# 7_dc_dc_3v3_eps_ttc.net
KiCad netlist of a schematic drawn in Altium Designer
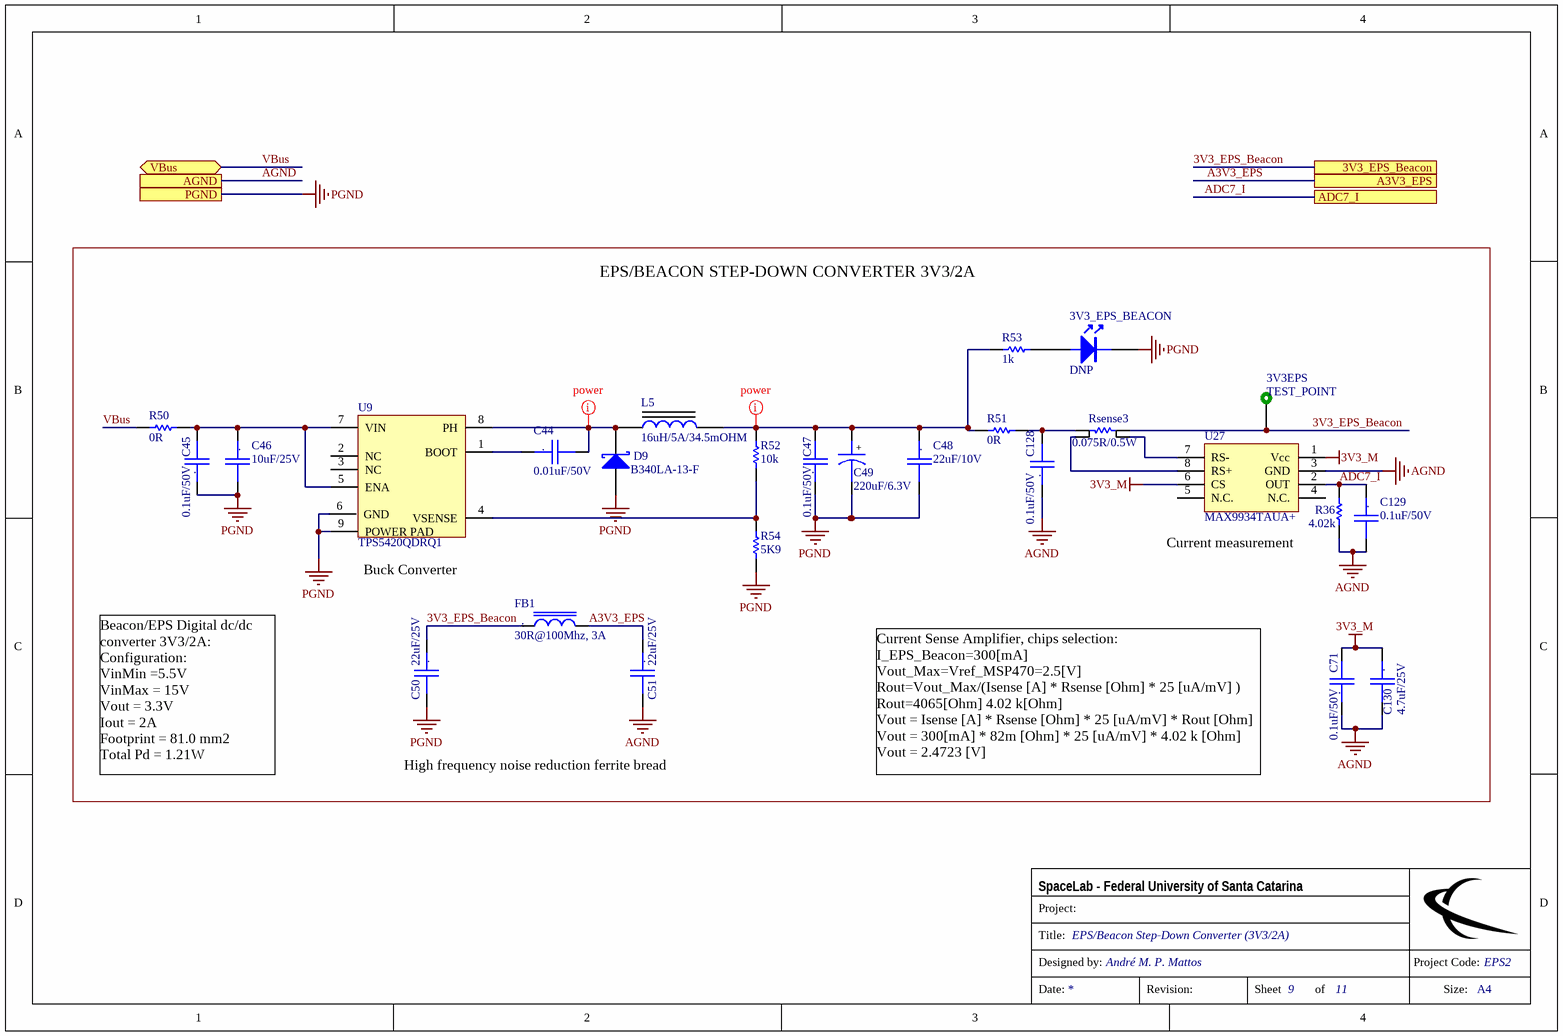
[diagram p0: 7_dc_dc_3v3_eps_ttc.schdoc]

(export (version "E")
  (design (tool "Eeschema 10.0.6"))
  (components
    (comp (ref "3V3EPS")
      (value "TEST_POINT")
      (footprint "TEST_POINT")
      (description "Test point")
      (libsource (lib "PCB_Project_FlightModel_EPS") (part "TEST_POINT"))
    )
    (comp (ref "3V3_EPS_BEACON")
      (value "DNP")
      (footprint "0603-LED")
      (description "SMD Green LED")
      (fields (field (name "PARTNUMBER") "150060VS75000") (field (name "MANUFACTURER") "Wurth Electronics"))
      (libsource (lib "PCB_Project_FlightModel_EPS") (part "LED/G_0603"))
    )
    (comp (ref "C44")
      (value "0.01uF/50V")
      (footprint "CC0805")
      (description "CAP CER 0.01uF 50V 10% X7R 0805")
      (fields (field (name "PARTNUMBER") "08055C103KAT4A") (field (name "MANUFACTURER") "Kyocera AVX"))
      (libsource (lib "PCB_Project_FlightModel_EPS") (part "Cap_Cer_X7R_0.01uF_50V_0805"))
    )
    (comp (ref "C45")
      (value "0.1uF/50V")
      (footprint "CC0805")
      (description "CAP CER 0.1UF 50V 10% X7R 0805")
      (fields (field (name "PARTNUMBER") "CC0805KRX7R9BB104") (field (name "MANUFACTURER") "Yageo"))
      (libsource (lib "PCB_Project_FlightModel_EPS") (part "Cap_Cer_X7R_0.1uF_50V_0805"))
    )
    (comp (ref "C46")
      (value "10uF/25V")
      (footprint "CC1206")
      (description "CAP CER 10uF 25V 10% X7R 1206")
      (fields (field (name "PARTNUMBER") "GRM31CR71E106KA12L") (field (name "MANUFACTURER") "Murata"))
      (libsource (lib "PCB_Project_FlightModel_EPS") (part "Cap_Cer_X7R_10uF_25V_1206"))
    )
    (comp (ref "C47")
      (value "0.1uF/50V")
      (footprint "CC0805")
      (description "CAP CER 0.1UF 50V 10% X7R 0805")
      (fields (field (name "PARTNUMBER") "CC0805KRX7R9BB104") (field (name "MANUFACTURER") "Yageo"))
      (libsource (lib "PCB_Project_FlightModel_EPS") (part "Cap_Cer_X7R_0.1uF_50V_0805"))
    )
    (comp (ref "C48")
      (value "22uF/10V")
      (footprint "CC1206")
      (description "CAP CER 22uF 10V 10% X7R 1206")
      (fields (field (name "PARTNUMBER") "GRM31CR71A226KE15L") (field (name "MANUFACTURER") "Murata"))
      (libsource (lib "PCB_Project_FlightModel_EPS") (part "Cap_Cer_X7R_22uF_10V_1206"))
    )
    (comp (ref "C49")
      (value "220uF/6.3V")
      (footprint "FloripaSatPcbLib:cc1210")
      (description "CAP Tantalum 220uF 6.3V 20% 1210")
      (fields (field (name "PARTNUMBER") "6TPE220MAZB") (field (name "MANUFACTURER") "Panasonic"))
      (libsource (lib "PCB_Project_FlightModel_EPS") (part "Cap_Tant_SMD_220uF_6.3V_1210"))
    )
    (comp (ref "C50")
      (value "22uF/25V")
      (footprint "CC1210")
      (description "CAP CER 22uF 25V 10% X7R 1210")
      (fields (field (name "PARTNUMBER") "GRM32ER71E226KE15L") (field (name "MANUFACTURER") "Murata"))
      (libsource (lib "PCB_Project_FlightModel_EPS") (part "Cap_Cer_X7R_22uF_25V_1210"))
    )
    (comp (ref "C51")
      (value "22uF/25V")
      (footprint "CC1210")
      (description "CAP CER 22uF 25V 10% X7R 1210")
      (fields (field (name "PARTNUMBER") "GRM32ER71E226KE15L") (field (name "MANUFACTURER") "Murata"))
      (libsource (lib "PCB_Project_FlightModel_EPS") (part "Cap_Cer_X7R_22uF_25V_1210"))
    )
    (comp (ref "C71")
      (value "0.1uF/50V")
      (footprint "CC0603")
      (description "CAP CER 0.1UF 50V 10% X7R 0603")
      (fields (field (name "PARTNUMBER") "CC0603KPX7R9BB104") (field (name "MANUFACTURER") "Yageo"))
      (libsource (lib "PCB_Project_FlightModel_EPS") (part "Cap_Cer_X7R_0.1uF_50V_0603"))
    )
    (comp (ref "C128")
      (value "0.1uF/50V")
      (footprint "CC0603")
      (description "CAP CER 0.1UF 50V 10% X7R 0603")
      (fields (field (name "PARTNUMBER") "CC0603KPX7R9BB104") (field (name "MANUFACTURER") "Yageo"))
      (libsource (lib "PCB_Project_FlightModel_EPS") (part "Cap_Cer_X7R_0.1uF_50V_0603"))
    )
    (comp (ref "C129")
      (value "0.1uF/50V")
      (footprint "CC0603")
      (description "CAP CER 0.1UF 50V 10% X7R 0603")
      (fields (field (name "PARTNUMBER") "CC0603KPX7R9BB104") (field (name "MANUFACTURER") "Yageo"))
      (libsource (lib "PCB_Project_FlightModel_EPS") (part "Cap_Cer_X7R_0.1uF_50V_0603"))
    )
    (comp (ref "C130")
      (value "4.7uF/25V")
      (footprint "CC0805")
      (description "CAP CER 4.7uF 25V 10% X7R 0805")
      (fields (field (name "PARTNUMBER") "CC0805KKX7R8BB475") (field (name "MANUFACTURER") "Yageo"))
      (libsource (lib "PCB_Project_FlightModel_EPS") (part "Cap_Cer_X7R_4.7uF_25V_0805"))
    )
    (comp (ref "D9")
      (value "B340LA-13-F")
      (footprint "DO-214AC")
      (description "DIODE SCHOTTKY 40V 3A B340LA-13-F")
      (fields (field (name "MANUFACTURER") "Diodes"))
      (libsource (lib "PCB_Project_FlightModel_EPS") (part "DIODE_SCHOTTKY_40V_3A_B340LA-13-F"))
    )
    (comp (ref "FB1")
      (value "30R@100Mhz, 3A")
      (footprint "IND0805")
      (description "Ferrite Bead 30 OHM 3A 100MHz")
      (fields (field (name "PARTNUMBER") "BLM21PG300SN1D") (field (name "MANUFACTURER") "Murata"))
      (libsource (lib "PCB_Project_FlightModel_EPS") (part "FB_30R_3A_100MHz_0805"))
    )
    (comp (ref "L5")
      (value "16uH/5A/34.5mOHM")
      (footprint "IND_744325xxx")
      (description "INDUCTOR 16UH 5A SMD")
      (fields (field (name "PARTNUMBER") "7443251600") (field (name "MANUFACTURER") "Wurth Electronics"))
      (libsource (lib "PCB_Project_FlightModel_EPS") (part "IND_POWER_16uH_5A_35.5mR"))
    )
    (comp (ref "R36")
      (value "4.02k")
      (footprint "0805")
      (description "RES 4.02k OHM 1/8W 0.1% 0805")
      (fields (field (name "PARTNUMBER") "ERA-6AEB4021V") (field (name "MANUFACTURER") "Panasonic"))
      (libsource (lib "PCB_Project_FlightModel_EPS") (part "R4.02k_0.1%_1/8W_0805"))
    )
    (comp (ref "R50")
      (value "0R")
      (footprint "1206")
      (description "RES 0.0 OHM 3/4W JUMP 1206")
      (fields
        (field (name "PARTNUMBER") "HCJ1206ZT0R00")
        (field (name "MANUFACTURER") "Stackpole Electronics")
      )
      (libsource (lib "PCB_Project_FlightModel_EPS") (part "R0R_JUMPER_3/4W_1206"))
    )
    (comp (ref "R51")
      (value "0R")
      (footprint "1206")
      (description "RES 0.0 OHM 3/4W JUMP 1206")
      (fields
        (field (name "PARTNUMBER") "HCJ1206ZT0R00")
        (field (name "MANUFACTURER") "Stackpole Electronics")
      )
      (libsource (lib "PCB_Project_FlightModel_EPS") (part "R0R_JUMPER_3/4W_1206"))
    )
    (comp (ref "R52")
      (value "10k")
      (footprint "0805")
      (description "RES 10K OHM 1/8W 1%  0805")
      (fields (field (name "PARTNUMBER") "CRCW080510K0FKEA") (field (name "MANUFACTURER") "Vishay"))
      (libsource (lib "PCB_Project_FlightModel_EPS") (part "R10k_1%_1/8W_0805"))
    )
    (comp (ref "R53")
      (value "1k")
      (footprint "0603")
      (description "RES 1.0K OHM 1/8W 1% 0603")
      (fields (field (name "PARTNUMBER") "MCT06030C1001FP500") (field (name "MANUFACTURER") "Vishay"))
      (libsource (lib "PCB_Project_FlightModel_EPS") (part "R1.0k_1%_1/8W_0603"))
    )
    (comp (ref "R54")
      (value "5K9")
      (footprint "0805")
      (description "RES 5K9 OHM 1/8W 1% 0805")
      (fields (field (name "PARTNUMBER") "71-CRCW0805-5.9K-E3") (field (name "MANUFACTURER") "Vishay"))
      (libsource (lib "PCB_Project_FlightModel_EPS") (part "R5.9K_1%_1/8W_0805"))
    )
    (comp (ref "Rsense3")
      (value "0.075R/0.5W")
      (footprint "1206 - ohmite")
      (description "Current Sense Resistors - SMD 1/2W 0.075 OHMS 1% 4 Terminal")
      (fields (field (name "PARTNUMBER") "LVK12R075FER") (field (name "MANUFACTURER") "Ohmite"))
      (libsource (lib "PCB_Project_FlightModel_EPS") (part "R0.075R_1%_0.5W_1206"))
    )
    (comp (ref "U9")
      (value "TPS5420QDRQ1")
      (footprint "SO8 Power PAD")
      (fields (field (name "MANUFACTURER") "Texas Instruments"))
      (libsource (lib "PCB_Project_FlightModel_EPS") (part "TPS5420QDRQ1"))
    )
    (comp (ref "U27")
      (value "MAX9934TAUA+")
      (footprint "MSOP-8")
      (fields (field (name "MANUFACTURER") "Maxim"))
      (libsource (lib "PCB_Project_FlightModel_EPS") (part "MAX9934TAUA+"))
    )
  )
  (nets
    (net (code "1") (name "/3V3_EPS_Beacon") (class "Default")
      (node (ref "3V3EPS") (pin "1") (pinfunction "1_1") (pintype "passive"))
      (node (ref "C50") (pin "1") (pinfunction "1_1") (pintype "passive"))
      (node (ref "FB1") (pin "1") (pinfunction "1_1") (pintype "passive"))
      (node (ref "Rsense3") (pin "2") (pinfunction "2_2") (pintype "passive"))
    )
    (net (code "2") (name "/A3V3_EPS") (class "Default")
      (node (ref "C51") (pin "1") (pinfunction "1_1") (pintype "passive"))
      (node (ref "FB1") (pin "2") (pinfunction "2_2") (pintype "passive"))
    )
    (net (code "3") (name "/ADC7_I") (class "Default")
      (node (ref "C129") (pin "1") (pinfunction "1_1") (pintype "passive"))
      (node (ref "R36") (pin "2") (pinfunction "2_2") (pintype "passive"))
      (node (ref "U27") (pin "2") (pinfunction "OUT_2") (pintype "passive"))
    )
    (net (code "4") (name "/VBus") (class "Default")
      (node (ref "R50") (pin "2") (pinfunction "2_2") (pintype "passive"))
    )
    (net (code "5") (name "3V3_M") (class "Default")
      (node (ref "C130") (pin "1") (pinfunction "1_1") (pintype "passive"))
      (node (ref "C71") (pin "2") (pinfunction "2_2") (pintype "passive"))
      (node (ref "U27") (pin "1") (pinfunction "Vcc_1") (pintype "passive"))
      (node (ref "U27") (pin "6") (pinfunction "CS_6") (pintype "passive"))
    )
    (net (code "6") (name "AGND") (class "Default")
      (node (ref "C128") (pin "1") (pinfunction "1_1") (pintype "passive"))
      (node (ref "C129") (pin "2") (pinfunction "2_2") (pintype "passive"))
      (node (ref "C130") (pin "2") (pinfunction "2_2") (pintype "passive"))
      (node (ref "C51") (pin "2") (pinfunction "2_2") (pintype "passive"))
      (node (ref "C71") (pin "1") (pinfunction "1_1") (pintype "passive"))
      (node (ref "R36") (pin "1") (pinfunction "1_1") (pintype "passive"))
      (node (ref "U27") (pin "3") (pinfunction "GND_3") (pintype "passive"))
    )
    (net (code "7") (name "Net-(3V3_EPS_BEACON-A)") (class "Default")
      (node (ref "3V3_EPS_BEACON") (pin "1") (pinfunction "A_1") (pintype "passive"))
      (node (ref "R53") (pin "1") (pinfunction "1_1") (pintype "passive"))
    )
    (net (code "8") (name "Net-(C47-Pad2)") (class "Default")
      (node (ref "C47") (pin "2") (pinfunction "2_2") (pintype "passive"))
      (node (ref "C48") (pin "1") (pinfunction "1_1") (pintype "passive"))
      (node (ref "C49") (pin "1") (pinfunction "1_1") (pintype "passive"))
      (node (ref "L5") (pin "2") (pinfunction "2_2") (pintype "passive"))
      (node (ref "R51") (pin "2") (pinfunction "2_2") (pintype "passive"))
      (node (ref "R52") (pin "2") (pinfunction "2_2") (pintype "passive"))
      (node (ref "R53") (pin "2") (pinfunction "2_2") (pintype "passive"))
    )
    (net (code "9") (name "Net-(C128-Pad2)") (class "Default")
      (node (ref "C128") (pin "2") (pinfunction "2_2") (pintype "passive"))
      (node (ref "R51") (pin "1") (pinfunction "1_1") (pintype "passive"))
      (node (ref "Rsense3") (pin "1") (pinfunction "1_1") (pintype "passive"))
    )
    (net (code "10") (name "Net-(D9-K)") (class "Default")
      (node (ref "C44") (pin "2") (pinfunction "2_2") (pintype "passive"))
      (node (ref "D9") (pin "1") (pinfunction "K_1") (pintype "passive"))
      (node (ref "L5") (pin "1") (pinfunction "1_1") (pintype "passive"))
      (node (ref "U9") (pin "8") (pinfunction "PH_8") (pintype "passive"))
    )
    (net (code "11") (name "Net-(U9-BOOT)") (class "Default")
      (node (ref "C44") (pin "1") (pinfunction "1_1") (pintype "passive"))
      (node (ref "U9") (pin "1") (pinfunction "BOOT_1") (pintype "passive"))
    )
    (net (code "12") (name "Net-(U9-ENA)") (class "Default")
      (node (ref "C45") (pin "2") (pinfunction "2_2") (pintype "passive"))
      (node (ref "C46") (pin "1") (pinfunction "1_1") (pintype "passive"))
      (node (ref "R50") (pin "1") (pinfunction "1_1") (pintype "passive"))
      (node (ref "U9") (pin "5") (pinfunction "ENA_5") (pintype "passive"))
      (node (ref "U9") (pin "7") (pinfunction "VIN_7") (pintype "passive"))
    )
    (net (code "13") (name "Net-(U9-VSENSE)") (class "Default")
      (node (ref "R52") (pin "1") (pinfunction "1_1") (pintype "passive"))
      (node (ref "R54") (pin "2") (pinfunction "2_2") (pintype "passive"))
      (node (ref "U9") (pin "4") (pinfunction "VSENSE_4") (pintype "passive"))
    )
    (net (code "14") (name "Net-(U27-RS+)") (class "Default")
      (node (ref "Rsense3") (pin "3") (pinfunction "3_3") (pintype "passive"))
      (node (ref "U27") (pin "8") (pinfunction "RS+_8") (pintype "passive"))
    )
    (net (code "15") (name "Net-(U27-RS-)") (class "Default")
      (node (ref "Rsense3") (pin "4") (pinfunction "4_4") (pintype "passive"))
      (node (ref "U27") (pin "7") (pinfunction "RS-_7") (pintype "passive"))
    )
    (net (code "16") (name "PGND") (class "Default")
      (node (ref "3V3_EPS_BEACON") (pin "2") (pinfunction "K_2") (pintype "passive"))
      (node (ref "C45") (pin "1") (pinfunction "1_1") (pintype "passive"))
      (node (ref "C46") (pin "2") (pinfunction "2_2") (pintype "passive"))
      (node (ref "C47") (pin "1") (pinfunction "1_1") (pintype "passive"))
      (node (ref "C48") (pin "2") (pinfunction "2_2") (pintype "passive"))
      (node (ref "C49") (pin "2") (pinfunction "2_2") (pintype "passive"))
      (node (ref "C50") (pin "2") (pinfunction "2_2") (pintype "passive"))
      (node (ref "D9") (pin "2") (pinfunction "A_2") (pintype "passive"))
      (node (ref "R54") (pin "1") (pinfunction "1_1") (pintype "passive"))
      (node (ref "U9") (pin "6") (pinfunction "GND_6") (pintype "passive"))
      (node (ref "U9") (pin "9") (pinfunction "POWER_PAD_9") (pintype "passive"))
    )
    (net (code "17") (name "unconnected-(U9-NC-Pad2)") (class "Default")
      (node (ref "U9") (pin "2") (pinfunction "NC_2") (pintype "passive"))
    )
    (net (code "18") (name "unconnected-(U9-NC-Pad3)") (class "Default")
      (node (ref "U9") (pin "3") (pinfunction "NC_3") (pintype "passive"))
    )
    (net (code "19") (name "unconnected-(U27-N.C.-Pad4)") (class "Default")
      (node (ref "U27") (pin "4") (pinfunction "N.C._4") (pintype "passive"))
    )
    (net (code "20") (name "unconnected-(U27-N.C.-Pad5)") (class "Default")
      (node (ref "U27") (pin "5") (pinfunction "N.C._5") (pintype "passive"))
    )
  )
)
